# SCH_Hacker-card_2024-08-21.net
KiCad netlist of a schematic drawn in EasyEDA
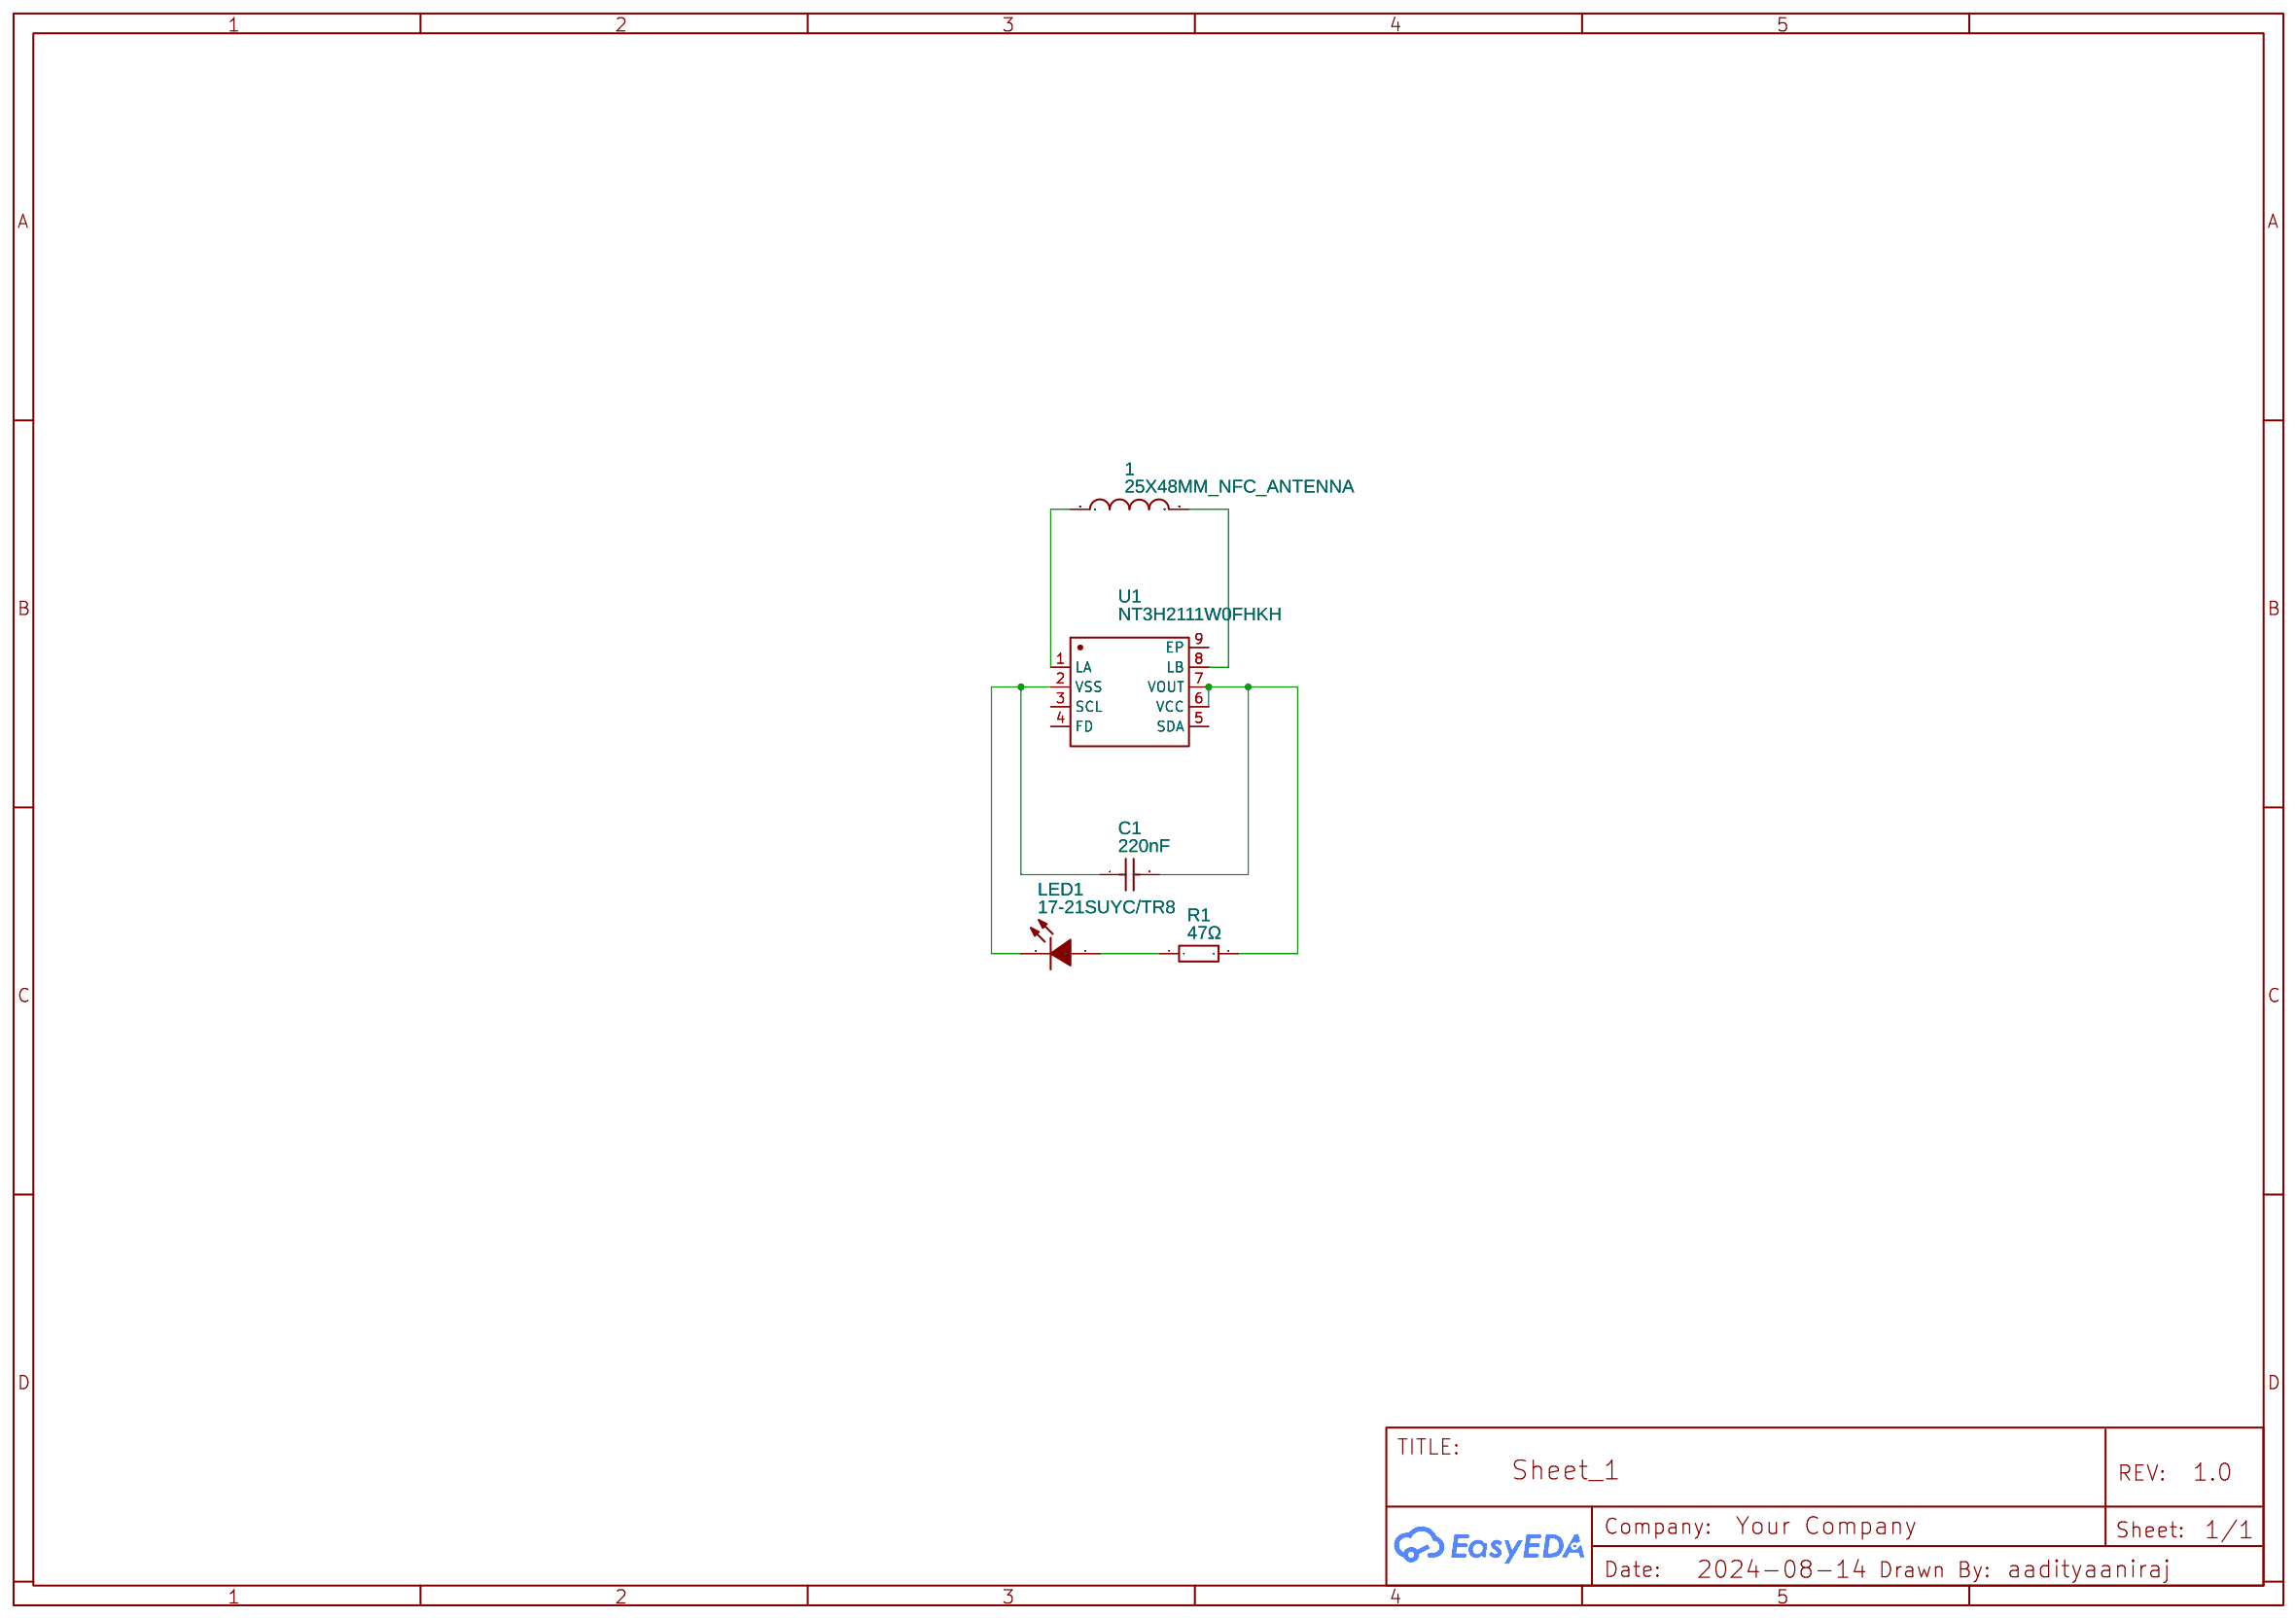
[diagram p0: schematic sheet]

(export (version "E")
  (design (tool "Eeschema 10.0.6"))
  (components
    (comp (ref "1") (value "25X48MM_NFC_ANTENNA") (libsource (lib "") (part "25X48MM_NFC_ANTENNA")))
    (comp (ref "C1")
      (value "220nF")
      (fields
        (field (name "Manufacturer Part") "CL10B224KA8NNNC")
        (field (name "Manufacturer") "SAMSUNG(三星)")
      )
      (libsource (lib "") (part "CL10B224KA8NNNC"))
    )
    (comp (ref "LED1")
      (value "17-21SUYC/TR8")
      (fields (field (name "Manufacturer Part") "KT-0805黄灯") (field (name "Manufacturer") "KENTO"))
      (libsource (lib "") (part "17-21SUYC/TR8"))
    )
    (comp (ref "R1")
      (value "47Ω")
      (fields
        (field (name "Manufacturer Part") "0603WAF470JT5E")
        (field (name "Manufacturer") "UNI-ROYAL(厚声)")
      )
      (libsource (lib "") (part "0603WAF470JT5E"))
    )
    (comp (ref "U1")
      (value "NT3H2111W0FHKH")
      (fields (field (name "Manufacturer") "NXP(恩智浦)"))
      (libsource (lib "") (part "NT3H2111W0FHKH"))
    )
  )
  (nets
    (net (code "1") (name "Net-(LED1-+)") (class "Default")
      (node (ref "LED1") (pin "1") (pinfunction "+_1") (pintype "unspecified"))
      (node (ref "R1") (pin "1") (pinfunction "1_1") (pintype "input"))
    )
    (net (code "2") (name "Net-(LED1--)") (class "Default")
      (node (ref "C1") (pin "1") (pinfunction "1_1") (pintype "input"))
      (node (ref "LED1") (pin "2") (pinfunction "-_2") (pintype "unspecified"))
      (node (ref "U1") (pin "2") (pinfunction "VSS_2") (pintype "unspecified"))
    )
    (net (code "3") (name "Net-(U1-LA)") (class "Default")
      (node (ref "1") (pin "P$1") (pinfunction "P$1_P$1") (pintype "bidirectional"))
      (node (ref "U1") (pin "1") (pinfunction "LA_1") (pintype "unspecified"))
    )
    (net (code "4") (name "Net-(U1-LB)") (class "Default")
      (node (ref "1") (pin "P$2") (pinfunction "P$2_P$2") (pintype "bidirectional"))
      (node (ref "U1") (pin "8") (pinfunction "LB_8") (pintype "unspecified"))
    )
    (net (code "5") (name "Net-(U1-VCC)") (class "Default")
      (node (ref "C1") (pin "2") (pinfunction "2_2") (pintype "input"))
      (node (ref "R1") (pin "2") (pinfunction "2_2") (pintype "input"))
      (node (ref "U1") (pin "6") (pinfunction "VCC_6") (pintype "unspecified"))
      (node (ref "U1") (pin "7") (pinfunction "VOUT_7") (pintype "unspecified"))
    )
    (net (code "6") (name "unconnected-(U1-EP-Pad9)") (class "Default")
      (node (ref "U1") (pin "9") (pinfunction "EP_9") (pintype "unspecified"))
    )
    (net (code "7") (name "unconnected-(U1-FD-Pad4)") (class "Default")
      (node (ref "U1") (pin "4") (pinfunction "FD_4") (pintype "unspecified"))
    )
    (net (code "8") (name "unconnected-(U1-SCL-Pad3)") (class "Default")
      (node (ref "U1") (pin "3") (pinfunction "SCL_3") (pintype "unspecified"))
    )
    (net (code "9") (name "unconnected-(U1-SDA-Pad5)") (class "Default")
      (node (ref "U1") (pin "5") (pinfunction "SDA_5") (pintype "unspecified"))
    )
  )
)
